# Workshop_1.net
KiCad netlist of a schematic drawn in Altium Designer
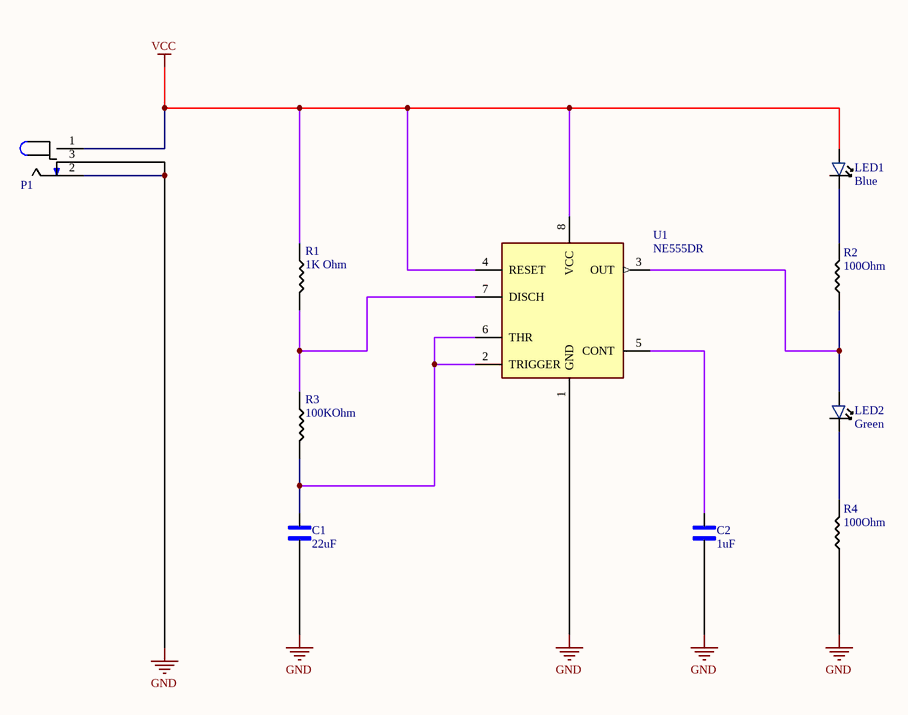
[diagram p0: Workshop_1.SchDoc]

(export (version "E")
  (design (tool "Eeschema 10.0.6"))
  (components
    (comp (ref "C1")
      (value "22uF")
      (footprint "1206_Passive_Capacitor")
      (description "22uF ±10% 25V X5R 1206 Multilayer Ceramic Capacitors MLCC - SMD/SMT RoHS")
      (fields (field (name "MFR PART #") "CL31A226KAHNNNE") (field (name "LCSC PART#") "C12891"))
      (libsource (lib "ECEN5730Lib_2023_05_DS") (part "C_22uF_1206"))
    )
    (comp (ref "C2")
      (value "1uF")
      (footprint "1206_Passive_Capacitor")
      (description "MULTILAYER CERAMIC CAPACITORS MLCC - SMD/SMT 1UF 50V 1206 ROHS")
      (fields (field (name "MFR PART #") "CL31B105KBHNNNE") (field (name "LCSC PART#") "C1848"))
      (libsource (lib "ECEN5730Lib_2023_05_DS") (part "C_1uF_1206"))
    )
    (comp (ref "LED1")
      (value "Blue")
      (footprint "LED_1206")
      (description "blue 1206  Light Emitting Diodes (LED) ROHS")
      (fields (field (name "MFR PART #") "NCD1206B1") (field (name "LCSC PART#") "C130717"))
      (libsource (lib "ECEN5730Lib_2023_05_DS") (part "LED_BLUE_1206"))
    )
    (comp (ref "LED2")
      (value "Green")
      (footprint "LED_1206")
      (description "Green 513~528nm 1206 Light Emitting Diodes (LED) RoHS")
      (fields (field (name "MFR PART #") "SZYY1206G") (field (name "LCSC PART#") "C434439"))
      (libsource (lib "ECEN5730Lib_2023_05_DS") (part "LED_GREEN_1206"))
    )
    (comp (ref "P1")
      (value "Power Jack")
      (footprint "Power_Jack")
      (description "Power Barrel Connector Jack 2.10mm ID (0.083\"), 5.50mm OD (0.217\") Through Hole, Right Angle")
      (fields (field (name "MFR PART #") "PJ-102A") (field (name "LCSC PART#") "C136744"))
      (libsource (lib "ECEN5730Lib_2023_05_DS") (part "P_Power Jack"))
    )
    (comp (ref "R1")
      (value "1K Ohm")
      (footprint "1206_Passive_Resitor")
      (description "CHIP RESISTOR - SURFACE MOUNT 1KOHMS ±1% 1/4W 1206 ROHS")
      (fields (field (name "MFR PART #") "RNCP1206FTD1K00CT") (field (name "LCSC PART#") "C4410"))
      (libsource (lib "ECEN5730Lib_2023_05_DS") (part "R_1K_1206"))
    )
    (comp (ref "R2")
      (value "100Ohm")
      (footprint "1206_Passive_Resitor")
      (description "100Ω ±1% 0.25W ±100ppm/℃ 1206 Chip Resistor - Surface Mount RoHS")
      (fields (field (name "LCSC PART#") "C17901") (field (name "MFR PART #") "1206W4F1000T5E"))
      (libsource (lib "ECEN5730Lib_2023_05_DS") (part "R_100Ohm_1206"))
    )
    (comp (ref "R3")
      (value "100KOhm")
      (footprint "1206_Passive_Resitor")
      (description "100kΩ ±1% 0.25W ±100ppm/℃ 1206 Chip Resistor - Surface Mount RoHS")
      (fields (field (name "LCSC PART#") "C17900") (field (name "MFR PART #") "1206W4F1003T5E"))
      (libsource (lib "ECEN5730Lib_2023_05_DS") (part "R_100KOhm_1206"))
    )
    (comp (ref "R4")
      (value "100Ohm")
      (footprint "1206_Passive_Resitor")
      (description "100Ω ±1% 0.25W ±100ppm/℃ 1206 Chip Resistor - Surface Mount RoHS")
      (fields (field (name "LCSC PART#") "C17901") (field (name "MFR PART #") "1206W4F1000T5E"))
      (libsource (lib "ECEN5730Lib_2023_05_DS") (part "R_100Ohm_1206"))
    )
    (comp (ref "U1")
      (value "NE555DR")
      (footprint "TS555IDTTR")
      (description "555 Timer SOIC-8_150MIL ROHS 150ns Rise Time")
      (fields (field (name "LCSC PART#") "C7593"))
      (libsource (lib "ECEN5730Lib_2023_05_DS") (part "U_555_Slow"))
    )
  )
  (nets
    (net (code "1") (name "GND") (class "Default")
      (node (ref "C1") (pin "1") (pinfunction "1_1") (pintype "passive"))
      (node (ref "C2") (pin "1") (pinfunction "1_1") (pintype "passive"))
      (node (ref "P1") (pin "2") (pinfunction "2_2") (pintype "power_in"))
      (node (ref "P1") (pin "3") (pinfunction "3_3") (pintype "power_in"))
      (node (ref "R4") (pin "1") (pinfunction "1_1") (pintype "passive"))
      (node (ref "U1") (pin "1") (pinfunction "GND_1") (pintype "power_in"))
    )
    (net (code "2") (name "Net-(LED1-Pad2)") (class "Default")
      (node (ref "LED1") (pin "2") (pinfunction "2_2") (pintype "passive"))
      (node (ref "R2") (pin "2") (pinfunction "2_2") (pintype "passive"))
    )
    (net (code "3") (name "Net-(LED2-Pad2)") (class "Default")
      (node (ref "LED2") (pin "2") (pinfunction "2_2") (pintype "passive"))
      (node (ref "R4") (pin "2") (pinfunction "2_2") (pintype "passive"))
    )
    (net (code "4") (name "Net-(U1-CONT)") (class "Default")
      (node (ref "C2") (pin "2") (pinfunction "2_2") (pintype "passive"))
      (node (ref "U1") (pin "5") (pinfunction "CONT_5") (pintype "passive"))
    )
    (net (code "5") (name "Net-(U1-DISCH)") (class "Default")
      (node (ref "R1") (pin "2") (pinfunction "2_2") (pintype "passive"))
      (node (ref "R3") (pin "1") (pinfunction "1_1") (pintype "passive"))
      (node (ref "U1") (pin "7") (pinfunction "DISCH_7") (pintype "passive"))
    )
    (net (code "6") (name "Net-(U1-OUT)") (class "Default")
      (node (ref "LED2") (pin "1") (pinfunction "1_1") (pintype "passive"))
      (node (ref "R2") (pin "1") (pinfunction "1_1") (pintype "passive"))
      (node (ref "U1") (pin "3") (pinfunction "OUT_3") (pintype "output"))
    )
    (net (code "7") (name "Net-(U1-THR)") (class "Default")
      (node (ref "C1") (pin "2") (pinfunction "2_2") (pintype "passive"))
      (node (ref "R3") (pin "2") (pinfunction "2_2") (pintype "passive"))
      (node (ref "U1") (pin "2") (pinfunction "TRIGGER_2") (pintype "passive"))
      (node (ref "U1") (pin "6") (pinfunction "THR_6") (pintype "passive"))
    )
    (net (code "8") (name "VCC") (class "Default")
      (node (ref "LED1") (pin "1") (pinfunction "1_1") (pintype "passive"))
      (node (ref "P1") (pin "1") (pinfunction "1_1") (pintype "power_in"))
      (node (ref "R1") (pin "1") (pinfunction "1_1") (pintype "passive"))
      (node (ref "U1") (pin "4") (pinfunction "RESET_4") (pintype "passive"))
      (node (ref "U1") (pin "8") (pinfunction "VCC_8") (pintype "power_in"))
    )
  )
)
